# finalmouse.net
KiCad netlist of a schematic drawn in EAGLE
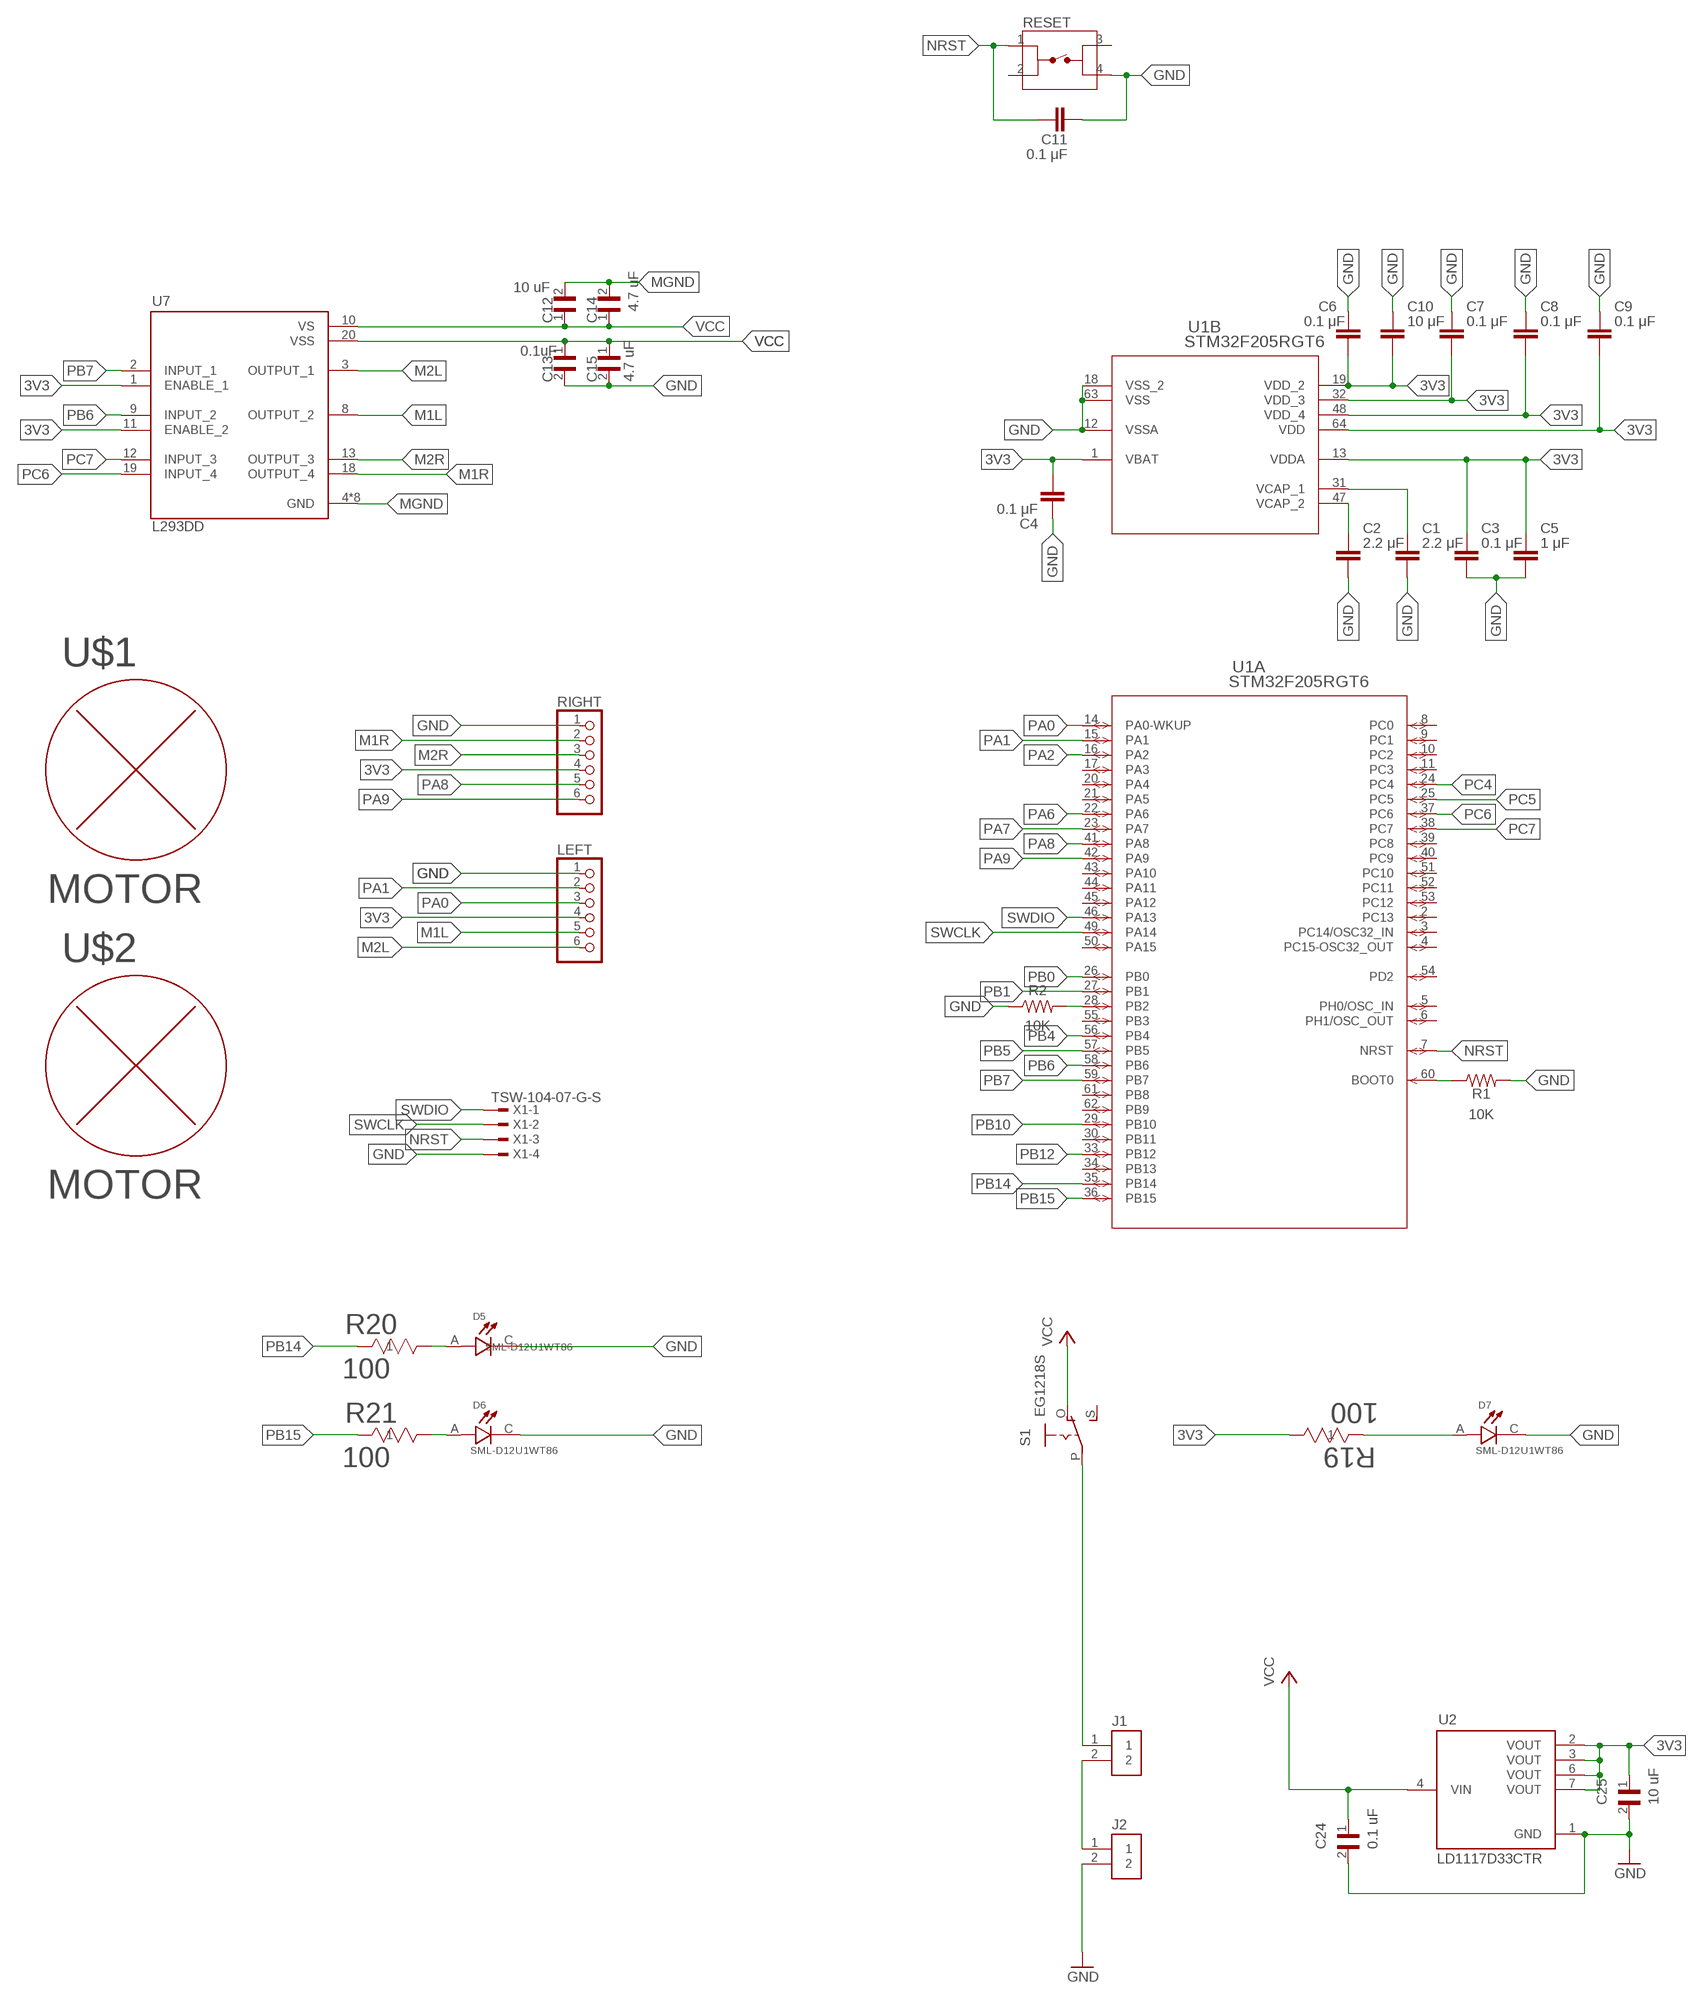
[diagram p0: schematic, sheet 1, part 1 of 2]
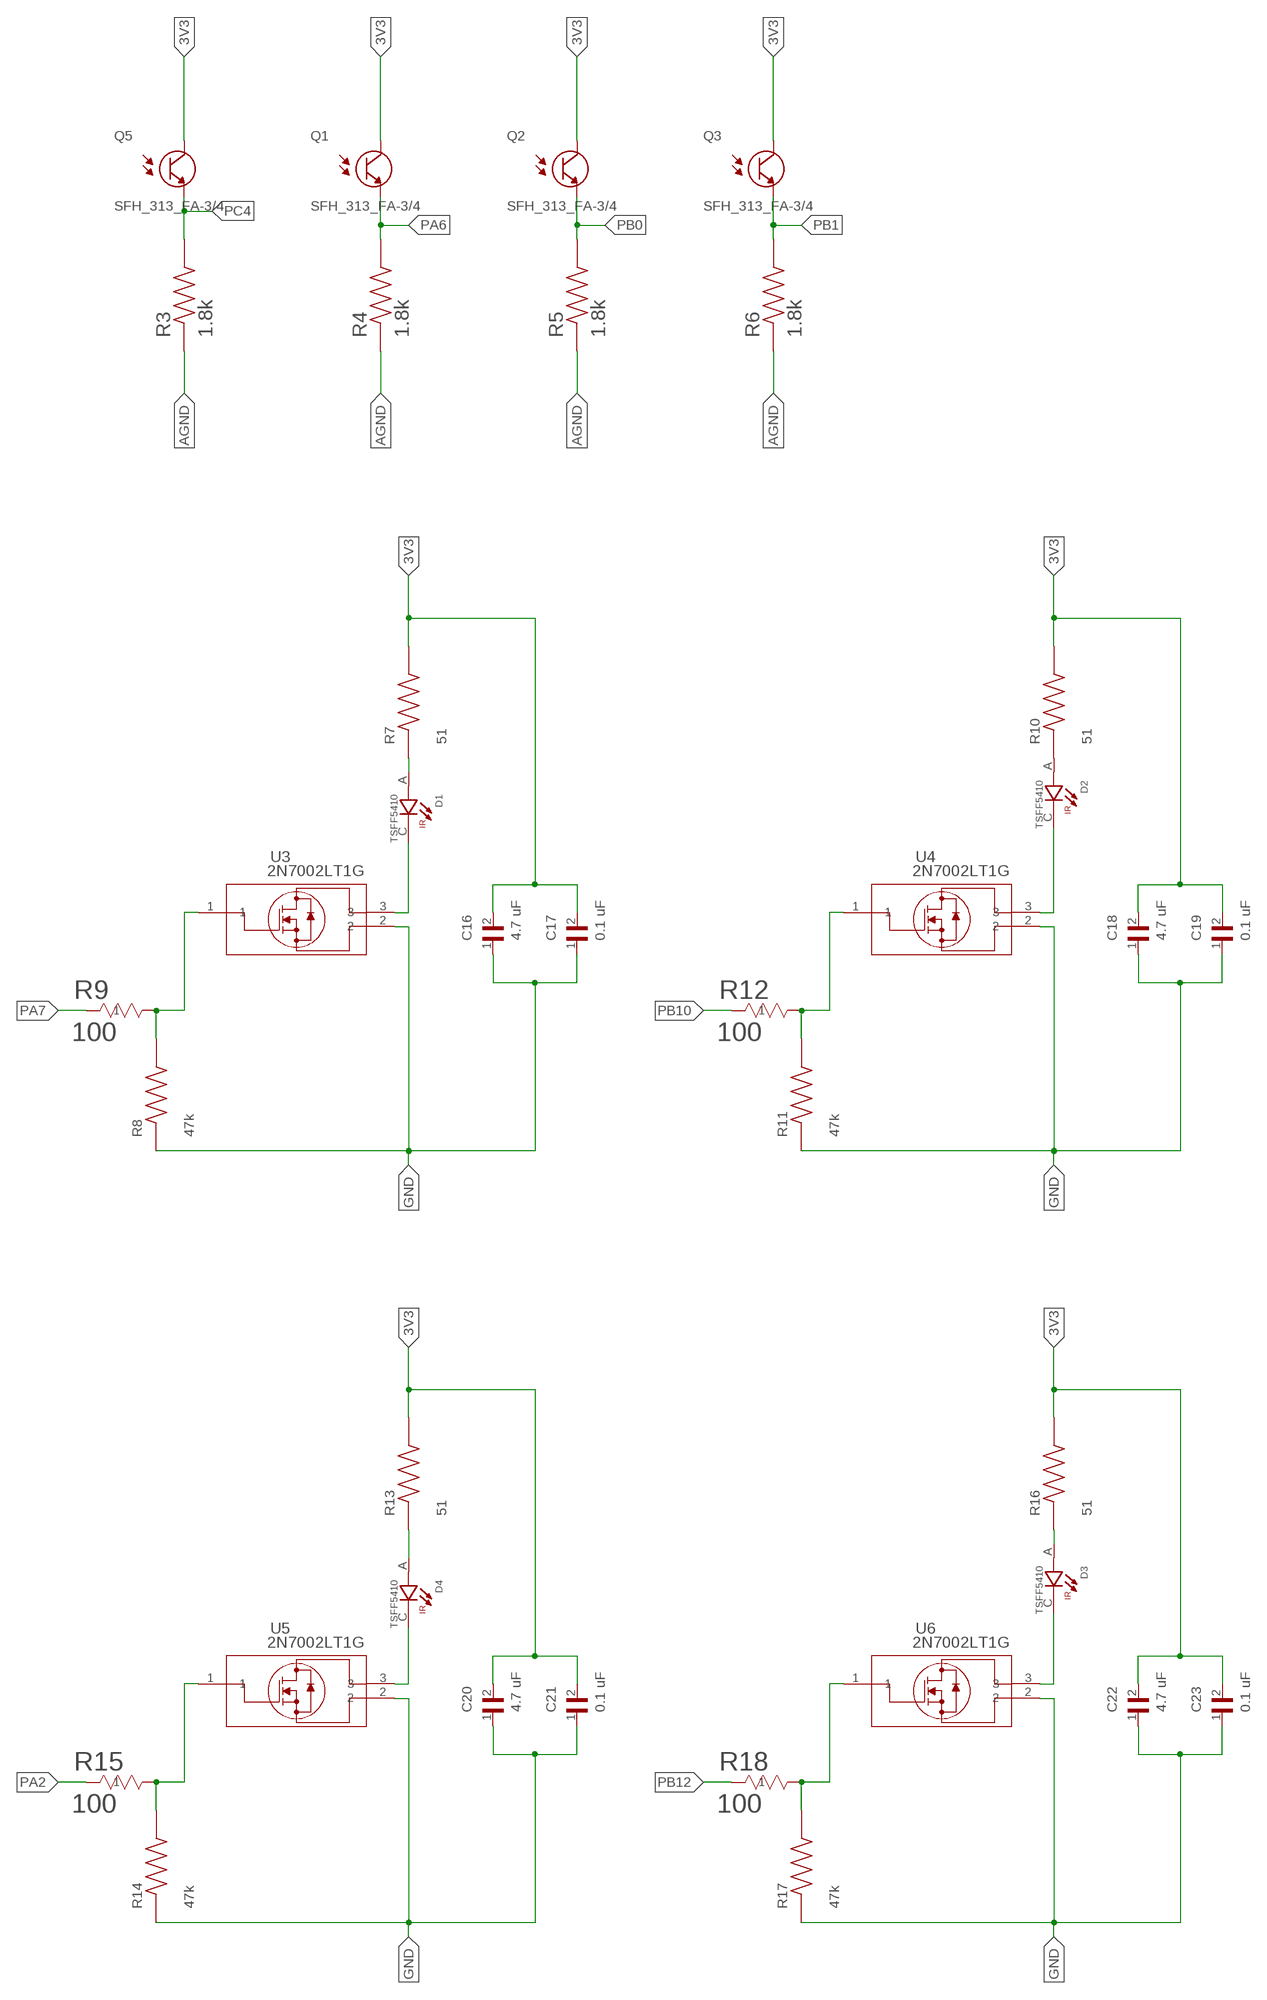
[diagram p1: schematic, sheet 1, part 2 of 2]

(export (version "E")
  (design (tool "Eeschema 10.0.6"))
  (components
    (comp (ref "C1")
      (value "2.2 μF")
      (footprint "eagle-import:CAPC1608X85")
      (libsource (lib "eagle-import") (part "CCHIP-0603(1608-METRIC)_"))
    )
    (comp (ref "C2")
      (value "2.2 μF")
      (footprint "eagle-import:CAPC1608X85")
      (libsource (lib "eagle-import") (part "CCHIP-0603(1608-METRIC)_"))
    )
    (comp (ref "C3")
      (value "0.1 μF")
      (footprint "eagle-import:CAPC1608X85")
      (libsource (lib "eagle-import") (part "CCHIP-0603(1608-METRIC)_"))
    )
    (comp (ref "C4")
      (value "0.1 μF")
      (footprint "eagle-import:CAPC1608X85")
      (libsource (lib "eagle-import") (part "CCHIP-0603(1608-METRIC)_"))
    )
    (comp (ref "C5")
      (value "1 μF")
      (footprint "eagle-import:CAPC1608X85")
      (libsource (lib "eagle-import") (part "CCHIP-0603(1608-METRIC)_"))
    )
    (comp (ref "C6")
      (value "0.1 μF")
      (footprint "eagle-import:CAPC1608X85")
      (libsource (lib "eagle-import") (part "CCHIP-0603(1608-METRIC)_"))
    )
    (comp (ref "C7")
      (value "0.1 μF")
      (footprint "eagle-import:CAPC1608X85")
      (libsource (lib "eagle-import") (part "Capacitor2_CCHIP-0603(1608-METRIC)_"))
    )
    (comp (ref "C8")
      (value "0.1 μF")
      (footprint "eagle-import:CAPC1608X85")
      (libsource (lib "eagle-import") (part "Capacitor2_CCHIP-0603(1608-METRIC)_"))
    )
    (comp (ref "C9")
      (value "0.1 μF")
      (footprint "eagle-import:CAPC1608X85")
      (libsource (lib "eagle-import") (part "Capacitor2_CCHIP-0603(1608-METRIC)_"))
    )
    (comp (ref "C10")
      (value "10 μF")
      (footprint "eagle-import:CAPC1608X85")
      (libsource (lib "eagle-import") (part "Capacitor2_CCHIP-0603(1608-METRIC)_"))
    )
    (comp (ref "C11")
      (value "0.1 μF")
      (footprint "eagle-import:CAPC1608X85")
      (libsource (lib "eagle-import") (part "Capacitor2_CCHIP-0603(1608-METRIC)_"))
    )
    (comp (ref "C12")
      (value "10 uF")
      (footprint "eagle-import:CAPC2012X135N")
      (fields
        (field (name "DIGI-KEY_PART_NUMBER") "1276-6456-2-ND")
        (field (name "MF") "Samsung Electro-Mechanics")
        (field (name "MP") "CL21A106KPFNNNG")
      )
      (libsource (lib "eagle-import") (part "CL21A106KPFNNNG"))
    )
    (comp (ref "C13")
      (value "0.1uF")
      (footprint "eagle-import:CAPC2012X94N")
      (fields
        (field (name "DIGI-KEY_PART_NUMBER") "478-5311-1-ND")
        (field (name "MF") "AVX")
        (field (name "MP") "08055C104K4T2A")
      )
      (libsource (lib "eagle-import") (part "08055C104K4T2A"))
    )
    (comp (ref "C14")
      (value "4.7 uF")
      (footprint "eagle-import:CAPC2012X145N")
      (fields
        (field (name "DIGI-KEY_PART_NUMBER") "445-11450-1-ND")
        (field (name "MF") "TDK")
        (field (name "MP") "C2012JB1C475K125AC")
      )
      (libsource (lib "eagle-import") (part "C2012JB1C475K125AC"))
    )
    (comp (ref "C15")
      (value "4.7 uF")
      (footprint "eagle-import:CAPC2012X145N")
      (fields
        (field (name "DIGI-KEY_PART_NUMBER") "445-11450-1-ND")
        (field (name "MF") "TDK")
        (field (name "MP") "C2012JB1C475K125AC")
      )
      (libsource (lib "eagle-import") (part "C2012JB1C475K125AC"))
    )
    (comp (ref "C16")
      (value "4.7 uF")
      (footprint "eagle-import:CAPC2012X145N")
      (fields
        (field (name "DIGI-KEY_PART_NUMBER") "445-11450-1-ND")
        (field (name "MF") "TDK")
        (field (name "MP") "C2012JB1C475K125AC")
      )
      (libsource (lib "eagle-import") (part "C2012JB1C475K125AC"))
    )
    (comp (ref "C17")
      (value "0.1 uF")
      (footprint "eagle-import:CAPC2012X94N")
      (fields
        (field (name "DIGI-KEY_PART_NUMBER") "478-5311-1-ND")
        (field (name "MF") "AVX")
        (field (name "MP") "08055C104K4T2A")
      )
      (libsource (lib "eagle-import") (part "08055C104K4T2A"))
    )
    (comp (ref "C18")
      (value "4.7 uF")
      (footprint "eagle-import:CAPC2012X145N")
      (fields
        (field (name "DIGI-KEY_PART_NUMBER") "445-11450-1-ND")
        (field (name "MF") "TDK")
        (field (name "MP") "C2012JB1C475K125AC")
      )
      (libsource (lib "eagle-import") (part "C2012JB1C475K125AC"))
    )
    (comp (ref "C19")
      (value "0.1 uF")
      (footprint "eagle-import:CAPC2012X94N")
      (fields
        (field (name "DIGI-KEY_PART_NUMBER") "478-5311-1-ND")
        (field (name "MF") "AVX")
        (field (name "MP") "08055C104K4T2A")
      )
      (libsource (lib "eagle-import") (part "08055C104K4T2A"))
    )
    (comp (ref "C20")
      (value "4.7 uF")
      (footprint "eagle-import:CAPC2012X145N")
      (fields
        (field (name "DIGI-KEY_PART_NUMBER") "445-11450-1-ND")
        (field (name "MF") "TDK")
        (field (name "MP") "C2012JB1C475K125AC")
      )
      (libsource (lib "eagle-import") (part "C2012JB1C475K125AC"))
    )
    (comp (ref "C21")
      (value "0.1 uF")
      (footprint "eagle-import:CAPC2012X94N")
      (fields
        (field (name "DIGI-KEY_PART_NUMBER") "478-5311-1-ND")
        (field (name "MF") "AVX")
        (field (name "MP") "08055C104K4T2A")
      )
      (libsource (lib "eagle-import") (part "08055C104K4T2A"))
    )
    (comp (ref "C22")
      (value "4.7 uF")
      (footprint "eagle-import:CAPC2012X145N")
      (fields
        (field (name "DIGI-KEY_PART_NUMBER") "445-11450-1-ND")
        (field (name "MF") "TDK")
        (field (name "MP") "C2012JB1C475K125AC")
      )
      (libsource (lib "eagle-import") (part "C2012JB1C475K125AC"))
    )
    (comp (ref "C23")
      (value "0.1 uF")
      (footprint "eagle-import:CAPC2012X94N")
      (fields
        (field (name "DIGI-KEY_PART_NUMBER") "478-5311-1-ND")
        (field (name "MF") "AVX")
        (field (name "MP") "08055C104K4T2A")
      )
      (libsource (lib "eagle-import") (part "08055C104K4T2A"))
    )
    (comp (ref "C24")
      (value "0.1 uF")
      (footprint "eagle-import:CAPC2012X135N")
      (fields
        (field (name "DIGI-KEY_PART_NUMBER") "1276-6456-2-ND")
        (field (name "MF") "Samsung Electro-Mechanics")
        (field (name "MP") "CL21A106KPFNNNG")
      )
      (libsource (lib "eagle-import") (part "CL21A106KPFNNNG"))
    )
    (comp (ref "C25")
      (value "10 uF")
      (footprint "eagle-import:CAPC2012X135N")
      (fields
        (field (name "DIGI-KEY_PART_NUMBER") "1276-2909-2-ND")
        (field (name "MF") "Samsung Electro-Mechanics")
        (field (name "MP") "CL21A226MOQNNNE")
      )
      (libsource (lib "eagle-import") (part "CL21A226MOQNNNE"))
    )
    (comp (ref "D1")
      (value "TSFF5410")
      (footprint "eagle-import:LEDRD254W55D595H1160")
      (fields (field (name "DIGI-KEY_PART_NUMBER") "751-1208-ND") (field (name "MF") "Vishay"))
      (libsource (lib "eagle-import") (part "TSFF5410"))
    )
    (comp (ref "D2")
      (value "TSFF5410")
      (footprint "eagle-import:LEDRD254W55D595H1160")
      (fields (field (name "DIGI-KEY_PART_NUMBER") "751-1208-ND") (field (name "MF") "Vishay"))
      (libsource (lib "eagle-import") (part "TSFF5410"))
    )
    (comp (ref "D3")
      (value "TSFF5410")
      (footprint "eagle-import:LEDRD254W55D595H1160")
      (fields (field (name "DIGI-KEY_PART_NUMBER") "751-1208-ND") (field (name "MF") "Vishay"))
      (libsource (lib "eagle-import") (part "TSFF5410"))
    )
    (comp (ref "D4")
      (value "TSFF5410")
      (footprint "eagle-import:LEDRD254W55D595H1160")
      (fields (field (name "DIGI-KEY_PART_NUMBER") "751-1208-ND") (field (name "MF") "Vishay"))
      (libsource (lib "eagle-import") (part "TSFF5410"))
    )
    (comp (ref "D5")
      (value "SML-D12U1WT86")
      (footprint "eagle-import:LED_SML-D12Y1WT86")
      (fields (field (name "DIGI-KEY_PART_NUMBER") "SML-D12U1WT86CT-ND") (field (name "MF") "Rohm"))
      (libsource (lib "eagle-import") (part "SML-D12U1WT86"))
    )
    (comp (ref "D6")
      (value "SML-D12U1WT86")
      (footprint "eagle-import:LED_SML-D12Y1WT86")
      (fields (field (name "DIGI-KEY_PART_NUMBER") "SML-D12U1WT86CT-ND") (field (name "MF") "Rohm"))
      (libsource (lib "eagle-import") (part "SML-D12U1WT86"))
    )
    (comp (ref "D7")
      (value "SML-D12U1WT86")
      (footprint "eagle-import:LED_SML-D12Y1WT86")
      (fields (field (name "DIGI-KEY_PART_NUMBER") "SML-D12U1WT86CT-ND") (field (name "MF") "Rohm"))
      (libsource (lib "eagle-import") (part "SML-D12U1WT86"))
    )
    (comp (ref "J1")
      (value "B2B-PH-K-S(LF)(SN)")
      (footprint "eagle-import:JST_B2B-PH-K-S(LF)(SN)")
      (fields (field (name "DIGI-KEY_PART_NUMBER") "455-1704-ND") (field (name "MF") "JST Sales"))
      (libsource (lib "eagle-import") (part "B2B-PH-K-S(LF)(SN)"))
    )
    (comp (ref "J2")
      (value "B2B-PH-K-S(LF)(SN)")
      (footprint "eagle-import:JST_B2B-PH-K-S(LF)(SN)")
      (fields (field (name "DIGI-KEY_PART_NUMBER") "455-1704-ND") (field (name "MF") "JST Sales"))
      (libsource (lib "eagle-import") (part "B2B-PH-K-S(LF)(SN)"))
    )
    (comp (ref "LEFT")
      (value "PINHD-1X6")
      (footprint "eagle-import:1X06")
      (libsource (lib "eagle-import") (part "PINHD-1X6"))
    )
    (comp (ref "Q1")
      (value "SFH_313_FA-3/4")
      (footprint "eagle-import:XDCR_SFH_313_FA-3_4")
      (fields (field (name "MF") "OSRAM Opto") (field (name "MP") "SFH 313 FA-3/4"))
      (libsource (lib "eagle-import") (part "SFH_313_FA-3/4"))
    )
    (comp (ref "Q2")
      (value "SFH_313_FA-3/4")
      (footprint "eagle-import:XDCR_SFH_313_FA-3_4")
      (fields (field (name "MF") "OSRAM Opto") (field (name "MP") "SFH 313 FA-3/4"))
      (libsource (lib "eagle-import") (part "SFH_313_FA-3/4"))
    )
    (comp (ref "Q3")
      (value "SFH_313_FA-3/4")
      (footprint "eagle-import:XDCR_SFH_313_FA-3_4")
      (fields (field (name "MF") "OSRAM Opto") (field (name "MP") "SFH 313 FA-3/4"))
      (libsource (lib "eagle-import") (part "SFH_313_FA-3/4"))
    )
    (comp (ref "Q5")
      (value "SFH_313_FA-3/4")
      (footprint "eagle-import:XDCR_SFH_313_FA-3_4")
      (fields (field (name "MF") "OSRAM Opto") (field (name "MP") "SFH 313 FA-3/4"))
      (libsource (lib "eagle-import") (part "SFH_313_FA-3/4"))
    )
    (comp (ref "R1")
      (value "10K")
      (footprint "eagle-import:RESC1608X60")
      (libsource (lib "eagle-import") (part "R-USCHIP-0603(1608-METRIC)_"))
    )
    (comp (ref "R2")
      (value "10K")
      (footprint "eagle-import:RESC1608X60")
      (libsource (lib "eagle-import") (part "R-USCHIP-0603(1608-METRIC)_"))
    )
    (comp (ref "R3")
      (value "1.8k")
      (footprint "eagle-import:RESC2012X65N")
      (fields
        (field (name "DIGI-KEY_PART_NUMBER") "RHM1.8KKCT-ND")
        (field (name "MF") "Rohm")
        (field (name "MP") "ESR10EZPJ182")
      )
      (libsource (lib "eagle-import") (part "ESR10EZPJ182"))
    )
    (comp (ref "R4")
      (value "1.8k")
      (footprint "eagle-import:RESC2012X65N")
      (fields
        (field (name "DIGI-KEY_PART_NUMBER") "RHM1.8KKCT-ND")
        (field (name "MF") "Rohm")
        (field (name "MP") "ESR10EZPJ182")
      )
      (libsource (lib "eagle-import") (part "ESR10EZPJ182"))
    )
    (comp (ref "R5")
      (value "1.8k")
      (footprint "eagle-import:RESC2012X65N")
      (fields
        (field (name "DIGI-KEY_PART_NUMBER") "RHM1.8KKCT-ND")
        (field (name "MF") "Rohm")
        (field (name "MP") "ESR10EZPJ182")
      )
      (libsource (lib "eagle-import") (part "ESR10EZPJ182"))
    )
    (comp (ref "R6")
      (value "1.8k")
      (footprint "eagle-import:RESC2012X65N")
      (fields
        (field (name "DIGI-KEY_PART_NUMBER") "RHM1.8KKCT-ND")
        (field (name "MF") "Rohm")
        (field (name "MP") "ESR10EZPJ182")
      )
      (libsource (lib "eagle-import") (part "ESR10EZPJ182"))
    )
    (comp (ref "R7")
      (value "51")
      (footprint "eagle-import:RES_ERJP06J510V")
      (fields
        (field (name "DIGI-KEY_PART_NUMBER") "P51ADCT-ND")
        (field (name "MF") "Panasonic")
        (field (name "MP") "ERJP06J510V")
      )
      (libsource (lib "eagle-import") (part "ERJP06J510V"))
    )
    (comp (ref "R8")
      (value "47k")
      (footprint "eagle-import:RES_ERA6ARB473V")
      (fields
        (field (name "DIGI-KEY_PART_NUMBER") "P47KBRCT-ND")
        (field (name "MF") "Panasonic")
        (field (name "MP") "ERA6ARB473V")
      )
      (libsource (lib "eagle-import") (part "ERA6ARB473V"))
    )
    (comp (ref "R9")
      (value "100")
      (footprint "eagle-import:RES_RK73G2A_KOA")
      (fields
        (field (name "MANUFACTURER_PART_NUMBER") "RK73G2ATTD1000D")
        (field (name "COPYRIGHT") "Copyright (C) 2022 Ultra Librarian. All rights reserved.")
      )
      (libsource (lib "eagle-import") (part "RK73G2ATTD1000D"))
    )
    (comp (ref "R10")
      (value "51")
      (footprint "eagle-import:RES_ERJP06J510V")
      (fields
        (field (name "DIGI-KEY_PART_NUMBER") "P51ADCT-ND")
        (field (name "MF") "Panasonic")
        (field (name "MP") "ERJP06J510V")
      )
      (libsource (lib "eagle-import") (part "ERJP06J510V"))
    )
    (comp (ref "R11")
      (value "47k")
      (footprint "eagle-import:RES_ERA6ARB473V")
      (fields
        (field (name "DIGI-KEY_PART_NUMBER") "P47KBRCT-ND")
        (field (name "MF") "Panasonic")
        (field (name "MP") "ERA6ARB473V")
      )
      (libsource (lib "eagle-import") (part "ERA6ARB473V"))
    )
    (comp (ref "R12")
      (value "100")
      (footprint "eagle-import:RES_RK73G2A_KOA")
      (fields
        (field (name "MANUFACTURER_PART_NUMBER") "RK73G2ATTD1000D")
        (field (name "COPYRIGHT") "Copyright (C) 2022 Ultra Librarian. All rights reserved.")
      )
      (libsource (lib "eagle-import") (part "RK73G2ATTD1000D"))
    )
    (comp (ref "R13")
      (value "51")
      (footprint "eagle-import:RES_ERJP06J510V")
      (fields
        (field (name "DIGI-KEY_PART_NUMBER") "P51ADCT-ND")
        (field (name "MF") "Panasonic")
        (field (name "MP") "ERJP06J510V")
      )
      (libsource (lib "eagle-import") (part "ERJP06J510V"))
    )
    (comp (ref "R14")
      (value "47k")
      (footprint "eagle-import:RES_ERA6ARB473V")
      (fields
        (field (name "DIGI-KEY_PART_NUMBER") "P47KBRCT-ND")
        (field (name "MF") "Panasonic")
        (field (name "MP") "ERA6ARB473V")
      )
      (libsource (lib "eagle-import") (part "ERA6ARB473V"))
    )
    (comp (ref "R15")
      (value "100")
      (footprint "eagle-import:RES_RK73G2A_KOA")
      (fields
        (field (name "MANUFACTURER_PART_NUMBER") "RK73G2ATTD1000D")
        (field (name "COPYRIGHT") "Copyright (C) 2022 Ultra Librarian. All rights reserved.")
      )
      (libsource (lib "eagle-import") (part "RK73G2ATTD1000D"))
    )
    (comp (ref "R16")
      (value "51")
      (footprint "eagle-import:RES_ERJP06J510V")
      (fields
        (field (name "DIGI-KEY_PART_NUMBER") "P51ADCT-ND")
        (field (name "MF") "Panasonic")
        (field (name "MP") "ERJP06J510V")
      )
      (libsource (lib "eagle-import") (part "ERJP06J510V"))
    )
    (comp (ref "R17")
      (value "47k")
      (footprint "eagle-import:RES_ERA6ARB473V")
      (fields
        (field (name "DIGI-KEY_PART_NUMBER") "P47KBRCT-ND")
        (field (name "MF") "Panasonic")
        (field (name "MP") "ERA6ARB473V")
      )
      (libsource (lib "eagle-import") (part "ERA6ARB473V"))
    )
    (comp (ref "R18")
      (value "100")
      (footprint "eagle-import:RES_RK73G2A_KOA")
      (fields
        (field (name "MANUFACTURER_PART_NUMBER") "RK73G2ATTD1000D")
        (field (name "COPYRIGHT") "Copyright (C) 2022 Ultra Librarian. All rights reserved.")
      )
      (libsource (lib "eagle-import") (part "RK73G2ATTD1000D"))
    )
    (comp (ref "R19")
      (value "100")
      (footprint "eagle-import:RES_RK73G2A_KOA")
      (fields
        (field (name "MANUFACTURER_PART_NUMBER") "RK73G2ATTD1000D")
        (field (name "COPYRIGHT") "Copyright (C) 2022 Ultra Librarian. All rights reserved.")
      )
      (libsource (lib "eagle-import") (part "RK73G2ATTD1000D"))
    )
    (comp (ref "R20")
      (value "100")
      (footprint "eagle-import:RES_RK73G2A_KOA")
      (fields
        (field (name "MANUFACTURER_PART_NUMBER") "RK73G2ATTD1000D")
        (field (name "COPYRIGHT") "Copyright (C) 2022 Ultra Librarian. All rights reserved.")
      )
      (libsource (lib "eagle-import") (part "RK73G2ATTD1000D"))
    )
    (comp (ref "R21")
      (value "100")
      (footprint "eagle-import:RES_RK73G2A_KOA")
      (fields
        (field (name "MANUFACTURER_PART_NUMBER") "RK73G2ATTD1000D")
        (field (name "COPYRIGHT") "Copyright (C) 2022 Ultra Librarian. All rights reserved.")
      )
      (libsource (lib "eagle-import") (part "RK73G2ATTD1000D"))
    )
    (comp (ref "RESET")
      (value "FSM4JSMA")
      (footprint "eagle-import:TE_FSM4JSMA")
      (fields
        (field (name "COMMENT") "4-1437565-1")
        (field (name "DIGI-KEY_PART_NUMBER") "450-1759-2-ND")
        (field (name "MF") "TE Connectivity")
      )
      (libsource (lib "eagle-import") (part "FSM4JSMA"))
    )
    (comp (ref "RIGHT")
      (value "PINHD-1X6")
      (footprint "eagle-import:1X06")
      (libsource (lib "eagle-import") (part "PINHD-1X6"))
    )
    (comp (ref "S1")
      (value "EG1218S")
      (footprint "eagle-import:EG1218")
      (fields
        (field (name "DIGI-KEY_PART_NUMBER") "EG1218A-ND")
        (field (name "MF") "E-Switch")
        (field (name "MP") "EG1218")
      )
      (libsource (lib "eagle-import") (part "EG1218S"))
    )
    (comp (ref "U$1")
      (value "MOTOR")
      (footprint "eagle-import:MOTOR")
      (libsource (lib "eagle-import") (part "MOTOR"))
    )
    (comp (ref "U$2")
      (value "MOTOR")
      (footprint "eagle-import:MOTOR")
      (libsource (lib "eagle-import") (part "MOTOR"))
    )
    (comp (ref "U1")
      (value "STM32F205RGT6")
      (footprint "eagle-import:LQFP64-10X10MM")
      (fields (field (name "COPYRIGHT") "Copyright (C) 2021 Ultra Librarian. All rights reserved."))
      (libsource (lib "eagle-import") (part "STM32F205RGT6"))
    )
    (comp (ref "U2")
      (value "LD1117D33CTR")
      (footprint "eagle-import:SOIC127P600X175-8N")
      (fields (field (name "DIGI-KEY_PART_NUMBER") "497-1230-1-ND") (field (name "MF") "STMicroelectronics"))
      (libsource (lib "eagle-import") (part "LD1117D33CTR"))
    )
    (comp (ref "U3")
      (value "2N7002LT1G")
      (footprint "eagle-import:SOT-23_3L_ONS")
      (fields (field (name "COPYRIGHT") "Copyright (C) 2022 Ultra Librarian. All rights reserved."))
      (libsource (lib "eagle-import") (part "2N7002LT1G"))
    )
    (comp (ref "U4")
      (value "2N7002LT1G")
      (footprint "eagle-import:SOT-23_3L_ONS")
      (fields (field (name "COPYRIGHT") "Copyright (C) 2022 Ultra Librarian. All rights reserved."))
      (libsource (lib "eagle-import") (part "2N7002LT1G"))
    )
    (comp (ref "U5")
      (value "2N7002LT1G")
      (footprint "eagle-import:SOT-23_3L_ONS")
      (fields (field (name "COPYRIGHT") "Copyright (C) 2022 Ultra Librarian. All rights reserved."))
      (libsource (lib "eagle-import") (part "2N7002LT1G"))
    )
    (comp (ref "U6")
      (value "2N7002LT1G")
      (footprint "eagle-import:SOT-23_3L_ONS")
      (fields (field (name "COPYRIGHT") "Copyright (C) 2022 Ultra Librarian. All rights reserved."))
      (libsource (lib "eagle-import") (part "2N7002LT1G"))
    )
    (comp (ref "U7")
      (value "L293DD")
      (footprint "eagle-import:SOIC127P1032X265-20N")
      (fields (field (name "DIGI-KEY_PART_NUMBER") "497-2937-2-ND") (field (name "MF") "STMicroelectronics"))
      (libsource (lib "eagle-import") (part "L293DD"))
    )
    (comp (ref "X1")
      (value "TSW-104-07-G-S")
      (footprint "eagle-import:TSW-104-XX-G-S")
      (fields (field (name "MF") "Samtec Inc."))
      (libsource (lib "eagle-import") (part "TSW-104--G-S07"))
    )
  )
  (nets
    (net (code "1") (name "3V3") (class "Default")
      (node (ref "C10") (pin "2") (pinfunction "2_2") (pintype "passive"))
      (node (ref "C16") (pin "2") (pinfunction "2_2") (pintype "passive"))
      (node (ref "C17") (pin "2") (pinfunction "2_2") (pintype "passive"))
      (node (ref "C18") (pin "2") (pinfunction "2_2") (pintype "passive"))
      (node (ref "C19") (pin "2") (pinfunction "2_2") (pintype "passive"))
      (node (ref "C20") (pin "2") (pinfunction "2_2") (pintype "passive"))
      (node (ref "C21") (pin "2") (pinfunction "2_2") (pintype "passive"))
      (node (ref "C22") (pin "2") (pinfunction "2_2") (pintype "passive"))
      (node (ref "C23") (pin "2") (pinfunction "2_2") (pintype "passive"))
      (node (ref "C25") (pin "1") (pinfunction "1_1") (pintype "passive"))
      (node (ref "C3") (pin "1") (pinfunction "1_1") (pintype "passive"))
      (node (ref "C4") (pin "2") (pinfunction "2_2") (pintype "passive"))
      (node (ref "C5") (pin "1") (pinfunction "1_1") (pintype "passive"))
      (node (ref "C6") (pin "2") (pinfunction "2_2") (pintype "passive"))
      (node (ref "C7") (pin "2") (pinfunction "2_2") (pintype "passive"))
      (node (ref "C8") (pin "2") (pinfunction "2_2") (pintype "passive"))
      (node (ref "C9") (pin "2") (pinfunction "2_2") (pintype "passive"))
      (node (ref "LEFT") (pin "4") (pinfunction "4_4") (pintype "passive"))
      (node (ref "Q1") (pin "2") (pinfunction "C_2") (pintype "passive"))
      (node (ref "Q2") (pin "2") (pinfunction "C_2") (pintype "passive"))
      (node (ref "Q3") (pin "2") (pinfunction "C_2") (pintype "passive"))
      (node (ref "Q5") (pin "2") (pinfunction "C_2") (pintype "passive"))
      (node (ref "R10") (pin "2") (pinfunction "2_2") (pintype "passive"))
      (node (ref "R13") (pin "2") (pinfunction "2_2") (pintype "passive"))
      (node (ref "R16") (pin "2") (pinfunction "2_2") (pintype "passive"))
      (node (ref "R19") (pin "2") (pinfunction "2_2") (pintype "passive"))
      (node (ref "R7") (pin "2") (pinfunction "2_2") (pintype "passive"))
      (node (ref "RIGHT") (pin "4") (pinfunction "4_4") (pintype "passive"))
      (node (ref "U1") (pin "1") (pinfunction "VBAT_1") (pintype "power_in"))
      (node (ref "U1") (pin "13") (pinfunction "VDDA_13") (pintype "power_in"))
      (node (ref "U1") (pin "19") (pinfunction "VDD_2_19") (pintype "power_in"))
      (node (ref "U1") (pin "32") (pinfunction "VDD_3_32") (pintype "power_in"))
      (node (ref "U1") (pin "48") (pinfunction "VDD_4_48") (pintype "power_in"))
      (node (ref "U1") (pin "64") (pinfunction "VDD_64") (pintype "power_in"))
      (node (ref "U2") (pin "2") (pinfunction "VOUT_2") (pintype "output"))
      (node (ref "U2") (pin "3") (pinfunction "VOUT_3") (pintype "output"))
      (node (ref "U2") (pin "6") (pinfunction "VOUT_6") (pintype "output"))
      (node (ref "U2") (pin "7") (pinfunction "VOUT_7") (pintype "output"))
      (node (ref "U7") (pin "1") (pinfunction "ENABLE_1_1") (pintype "input"))
      (node (ref "U7") (pin "11") (pinfunction "ENABLE_2_11") (pintype "input"))
    )
    (net (code "2") (name "AGND") (class "Default")
      (node (ref "R3") (pin "1") (pinfunction "1_1") (pintype "passive"))
      (node (ref "R4") (pin "1") (pinfunction "1_1") (pintype "passive"))
      (node (ref "R5") (pin "1") (pinfunction "1_1") (pintype "passive"))
      (node (ref "R6") (pin "1") (pinfunction "1_1") (pintype "passive"))
    )
    (net (code "3") (name "GND") (class "Default")
      (node (ref "C1") (pin "2") (pinfunction "2_2") (pintype "passive"))
      (node (ref "C10") (pin "1") (pinfunction "1_1") (pintype "passive"))
      (node (ref "C11") (pin "2") (pinfunction "2_2") (pintype "passive"))
      (node (ref "C13") (pin "2") (pinfunction "2_2") (pintype "passive"))
      (node (ref "C15") (pin "2") (pinfunction "2_2") (pintype "passive"))
      (node (ref "C16") (pin "1") (pinfunction "1_1") (pintype "passive"))
      (node (ref "C17") (pin "1") (pinfunction "1_1") (pintype "passive"))
      (node (ref "C18") (pin "1") (pinfunction "1_1") (pintype "passive"))
      (node (ref "C19") (pin "1") (pinfunction "1_1") (pintype "passive"))
      (node (ref "C2") (pin "2") (pinfunction "2_2") (pintype "passive"))
      (node (ref "C20") (pin "1") (pinfunction "1_1") (pintype "passive"))
      (node (ref "C21") (pin "1") (pinfunction "1_1") (pintype "passive"))
      (node (ref "C22") (pin "1") (pinfunction "1_1") (pintype "passive"))
      (node (ref "C23") (pin "1") (pinfunction "1_1") (pintype "passive"))
      (node (ref "C24") (pin "2") (pinfunction "2_2") (pintype "passive"))
      (node (ref "C25") (pin "2") (pinfunction "2_2") (pintype "passive"))
      (node (ref "C3") (pin "2") (pinfunction "2_2") (pintype "passive"))
      (node (ref "C4") (pin "1") (pinfunction "1_1") (pintype "passive"))
      (node (ref "C5") (pin "2") (pinfunction "2_2") (pintype "passive"))
      (node (ref "C6") (pin "1") (pinfunction "1_1") (pintype "passive"))
      (node (ref "C7") (pin "1") (pinfunction "1_1") (pintype "passive"))
      (node (ref "C8") (pin "1") (pinfunction "1_1") (pintype "passive"))
      (node (ref "C9") (pin "1") (pinfunction "1_1") (pintype "passive"))
      (node (ref "D5") (pin "C") (pinfunction "C_C") (pintype "passive"))
      (node (ref "D6") (pin "C") (pinfunction "C_C") (pintype "passive"))
      (node (ref "D7") (pin "C") (pinfunction "C_C") (pintype "passive"))
      (node (ref "J2") (pin "2") (pinfunction "2_2") (pintype "passive"))
      (node (ref "LEFT") (pin "1") (pinfunction "1_1") (pintype "passive"))
      (node (ref "R1") (pin "2") (pinfunction "2_2") (pintype "passive"))
      (node (ref "R11") (pin "1") (pinfunction "1_1") (pintype "passive"))
      (node (ref "R14") (pin "1") (pinfunction "1_1") (pintype "passive"))
      (node (ref "R17") (pin "1") (pinfunction "1_1") (pintype "passive"))
      (node (ref "R2") (pin "1") (pinfunction "1_1") (pintype "passive"))
      (node (ref "R8") (pin "1") (pinfunction "1_1") (pintype "passive"))
      (node (ref "RESET") (pin "4") (pinfunction "4_4") (pintype "passive"))
      (node (ref "RIGHT") (pin "1") (pinfunction "1_1") (pintype "passive"))
      (node (ref "U1") (pin "12") (pinfunction "VSSA_12") (pintype "power_in"))
      (node (ref "U1") (pin "18") (pinfunction "VSS_2_18") (pintype "power_in"))
      (node (ref "U1") (pin "63") (pinfunction "VSS_63") (pintype "power_in"))
      (node (ref "U2") (pin "1") (pinfunction "GND_1") (pintype "power_in"))
      (node (ref "U3") (pin "2") (pinfunction "2_2") (pintype "passive"))
      (node (ref "U4") (pin "2") (pinfunction "2_2") (pintype "passive"))
      (node (ref "U5") (pin "2") (pinfunction "2_2") (pintype "passive"))
      (node (ref "U6") (pin "2") (pinfunction "2_2") (pintype "passive"))
      (node (ref "X1") (pin "4") (pinfunction "1_4") (pintype "passive"))
    )
    (net (code "4") (name "M1L") (class "Default")
      (node (ref "LEFT") (pin "5") (pinfunction "5_5") (pintype "passive"))
      (node (ref "U7") (pin "8") (pinfunction "OUTPUT_2_8") (pintype "output"))
    )
    (net (code "5") (name "M1R") (class "Default")
      (node (ref "RIGHT") (pin "2") (pinfunction "2_2") (pintype "passive"))
      (node (ref "U7") (pin "18") (pinfunction "OUTPUT_4_18") (pintype "output"))
    )
    (net (code "6") (name "M2L") (class "Default")
      (node (ref "LEFT") (pin "6") (pinfunction "6_6") (pintype "passive"))
      (node (ref "U7") (pin "3") (pinfunction "OUTPUT_1_3") (pintype "output"))
    )
    (net (code "7") (name "M2R") (class "Default")
      (node (ref "RIGHT") (pin "3") (pinfunction "3_3") (pintype "passive"))
      (node (ref "U7") (pin "13") (pinfunction "OUTPUT_3_13") (pintype "output"))
    )
    (net (code "8") (name "MGND") (class "Default")
      (node (ref "C12") (pin "2") (pinfunction "2_2") (pintype "passive"))
      (node (ref "C14") (pin "2") (pinfunction "2_2") (pintype "passive"))
      (node (ref "U7") (pin "14") (pinfunction "GND_14") (pintype "power_in"))
      (node (ref "U7") (pin "15") (pinfunction "GND_15") (pintype "power_in"))
      (node (ref "U7") (pin "16") (pinfunction "GND_16") (pintype "power_in"))
      (node (ref "U7") (pin "17") (pinfunction "GND_17") (pintype "power_in"))
      (node (ref "U7") (pin "4") (pinfunction "GND_4") (pintype "power_in"))
      (node (ref "U7") (pin "5") (pinfunction "GND_5") (pintype "power_in"))
      (node (ref "U7") (pin "6") (pinfunction "GND_6") (pintype "power_in"))
      (node (ref "U7") (pin "7") (pinfunction "GND_7") (pintype "power_in"))
    )
    (net (code "9") (name "NRST") (class "Default")
      (node (ref "C11") (pin "1") (pinfunction "1_1") (pintype "passive"))
      (node (ref "RESET") (pin "1") (pinfunction "1_1") (pintype "passive"))
      (node (ref "U1") (pin "7") (pinfunction "NRST_7") (pintype "bidirectional"))
      (node (ref "X1") (pin "3") (pinfunction "1_3") (pintype "passive"))
    )
    (net (code "10") (name "Net-(D1-PadA)") (class "Default")
      (node (ref "D1") (pin "A") (pinfunction "A_A") (pintype "passive"))
      (node (ref "R7") (pin "1") (pinfunction "1_1") (pintype "passive"))
    )
    (net (code "11") (name "Net-(D1-PadC)") (class "Default")
      (node (ref "D1") (pin "C") (pinfunction "C_C") (pintype "passive"))
      (node (ref "U3") (pin "3") (pinfunction "3_3") (pintype "passive"))
    )
    (net (code "12") (name "Net-(D2-PadA)") (class "Default")
      (node (ref "D2") (pin "A") (pinfunction "A_A") (pintype "passive"))
      (node (ref "R10") (pin "1") (pinfunction "1_1") (pintype "passive"))
    )
    (net (code "13") (name "Net-(D2-PadC)") (class "Default")
      (node (ref "D2") (pin "C") (pinfunction "C_C") (pintype "passive"))
      (node (ref "U4") (pin "3") (pinfunction "3_3") (pintype "passive"))
    )
    (net (code "14") (name "Net-(D3-PadA)") (class "Default")
      (node (ref "D3") (pin "A") (pinfunction "A_A") (pintype "passive"))
      (node (ref "R16") (pin "1") (pinfunction "1_1") (pintype "passive"))
    )
    (net (code "15") (name "Net-(D3-PadC)") (class "Default")
      (node (ref "D3") (pin "C") (pinfunction "C_C") (pintype "passive"))
      (node (ref "U6") (pin "3") (pinfunction "3_3") (pintype "passive"))
    )
    (net (code "16") (name "Net-(D4-PadA)") (class "Default")
      (node (ref "D4") (pin "A") (pinfunction "A_A") (pintype "passive"))
      (node (ref "R13") (pin "1") (pinfunction "1_1") (pintype "passive"))
    )
    (net (code "17") (name "Net-(D4-PadC)") (class "Default")
      (node (ref "D4") (pin "C") (pinfunction "C_C") (pintype "passive"))
      (node (ref "U5") (pin "3") (pinfunction "3_3") (pintype "passive"))
    )
    (net (code "18") (name "Net-(D5-PadA)") (class "Default")
      (node (ref "D5") (pin "A") (pinfunction "A_A") (pintype "passive"))
      (node (ref "R20") (pin "2") (pinfunction "2_2") (pintype "passive"))
    )
    (net (code "19") (name "Net-(D6-PadA)") (class "Default")
      (node (ref "D6") (pin "A") (pinfunction "A_A") (pintype "passive"))
      (node (ref "R21") (pin "2") (pinfunction "2_2") (pintype "passive"))
    )
    (net (code "20") (name "Net-(D7-PadA)") (class "Default")
      (node (ref "D7") (pin "A") (pinfunction "A_A") (pintype "passive"))
      (node (ref "R19") (pin "1") (pinfunction "1_1") (pintype "passive"))
    )
    (net (code "21") (name "Net-(J1-Pad1)") (class "Default")
      (node (ref "J1") (pin "1") (pinfunction "1_1") (pintype "passive"))
      (node (ref "S1") (pin "P") (pinfunction "P_P") (pintype "passive"))
    )
    (net (code "22") (name "Net-(J1-Pad2)") (class "Default")
      (node (ref "J1") (pin "2") (pinfunction "2_2") (pintype "passive"))
      (node (ref "J2") (pin "1") (pinfunction "1_1") (pintype "passive"))
    )
    (net (code "23") (name "Net-(R8-Pad2)") (class "Default")
      (node (ref "R8") (pin "2") (pinfunction "2_2") (pintype "passive"))
      (node (ref "R9") (pin "2") (pinfunction "2_2") (pintype "passive"))
      (node (ref "U3") (pin "1") (pinfunction "1_1") (pintype "passive"))
    )
    (net (code "24") (name "Net-(R11-Pad2)") (class "Default")
      (node (ref "R11") (pin "2") (pinfunction "2_2") (pintype "passive"))
      (node (ref "R12") (pin "2") (pinfunction "2_2") (pintype "passive"))
      (node (ref "U4") (pin "1") (pinfunction "1_1") (pintype "passive"))
    )
    (net (code "25") (name "Net-(R14-Pad2)") (class "Default")
      (node (ref "R14") (pin "2") (pinfunction "2_2") (pintype "passive"))
      (node (ref "R15") (pin "2") (pinfunction "2_2") (pintype "passive"))
      (node (ref "U5") (pin "1") (pinfunction "1_1") (pintype "passive"))
    )
    (net (code "26") (name "Net-(R17-Pad2)") (class "Default")
      (node (ref "R17") (pin "2") (pinfunction "2_2") (pintype "passive"))
      (node (ref "R18") (pin "2") (pinfunction "2_2") (pintype "passive"))
      (node (ref "U6") (pin "1") (pinfunction "1_1") (pintype "passive"))
    )
    (net (code "27") (name "Net-(U1A-BOOT0)") (class "Default")
      (node (ref "R1") (pin "1") (pinfunction "1_1") (pintype "passive"))
      (node (ref "U1") (pin "60") (pinfunction "BOOT0_60") (pintype "input"))
    )
    (net (code "28") (name "Net-(U1A-PB2)") (class "Default")
      (node (ref "R2") (pin "2") (pinfunction "2_2") (pintype "passive"))
      (node (ref "U1") (pin "28") (pinfunction "PB2_28") (pintype "bidirectional"))
    )
    (net (code "29") (name "Net-(U1B-VCAP_1)") (class "Default")
      (node (ref "C1") (pin "1") (pinfunction "1_1") (pintype "passive"))
      (node (ref "U1") (pin "31") (pinfunction "VCAP_1_31") (pintype "power_in"))
    )
    (net (code "30") (name "Net-(U1B-VCAP_2)") (class "Default")
      (node (ref "C2") (pin "1") (pinfunction "1_1") (pintype "passive"))
      (node (ref "U1") (pin "47") (pinfunction "VCAP_2_47") (pintype "power_in"))
    )
    (net (code "31") (name "PA0") (class "Default")
      (node (ref "LEFT") (pin "3") (pinfunction "3_3") (pintype "passive"))
      (node (ref "U1") (pin "14") (pinfunction "PA0-WKUP_14") (pintype "bidirectional"))
    )
    (net (code "32") (name "PA1") (class "Default")
      (node (ref "LEFT") (pin "2") (pinfunction "2_2") (pintype "passive"))
      (node (ref "U1") (pin "15") (pinfunction "PA1_15") (pintype "bidirectional"))
    )
    (net (code "33") (name "PA2") (class "Default")
      (node (ref "R15") (pin "1") (pinfunction "1_1") (pintype "passive"))
      (node (ref "U1") (pin "16") (pinfunction "PA2_16") (pintype "bidirectional"))
    )
    (net (code "34") (name "PA6") (class "Default")
      (node (ref "Q1") (pin "1") (pinfunction "E_1") (pintype "passive"))
      (node (ref "R4") (pin "2") (pinfunction "2_2") (pintype "passive"))
      (node (ref "U1") (pin "22") (pinfunction "PA6_22") (pintype "bidirectional"))
    )
    (net (code "35") (name "PA7") (class "Default")
      (node (ref "R9") (pin "1") (pinfunction "1_1") (pintype "passive"))
      (node (ref "U1") (pin "23") (pinfunction "PA7_23") (pintype "bidirectional"))
    )
    (net (code "36") (name "PA8") (class "Default")
      (node (ref "RIGHT") (pin "5") (pinfunction "5_5") (pintype "passive"))
      (node (ref "U1") (pin "41") (pinfunction "PA8_41") (pintype "bidirectional"))
    )
    (net (code "37") (name "PA9") (class "Default")
      (node (ref "RIGHT") (pin "6") (pinfunction "6_6") (pintype "passive"))
      (node (ref "U1") (pin "42") (pinfunction "PA9_42") (pintype "bidirectional"))
    )
    (net (code "38") (name "PB0") (class "Default")
      (node (ref "Q2") (pin "1") (pinfunction "E_1") (pintype "passive"))
      (node (ref "R5") (pin "2") (pinfunction "2_2") (pintype "passive"))
      (node (ref "U1") (pin "26") (pinfunction "PB0_26") (pintype "bidirectional"))
    )
    (net (code "39") (name "PB1") (class "Default")
      (node (ref "Q3") (pin "1") (pinfunction "E_1") (pintype "passive"))
      (node (ref "R6") (pin "2") (pinfunction "2_2") (pintype "passive"))
      (node (ref "U1") (pin "27") (pinfunction "PB1_27") (pintype "bidirectional"))
    )
    (net (code "40") (name "PB4") (class "Default")
      (node (ref "U1") (pin "56") (pinfunction "PB4_56") (pintype "bidirectional"))
    )
    (net (code "41") (name "PB5") (class "Default")
      (node (ref "U1") (pin "57") (pinfunction "PB5_57") (pintype "bidirectional"))
    )
    (net (code "42") (name "PB6") (class "Default")
      (node (ref "U1") (pin "58") (pinfunction "PB6_58") (pintype "bidirectional"))
      (node (ref "U7") (pin "9") (pinfunction "INPUT_2_9") (pintype "input"))
    )
    (net (code "43") (name "PB7") (class "Default")
      (node (ref "U1") (pin "59") (pinfunction "PB7_59") (pintype "bidirectional"))
      (node (ref "U7") (pin "2") (pinfunction "INPUT_1_2") (pintype "input"))
    )
    (net (code "44") (name "PB10") (class "Default")
      (node (ref "R12") (pin "1") (pinfunction "1_1") (pintype "passive"))
      (node (ref "U1") (pin "29") (pinfunction "PB10_29") (pintype "bidirectional"))
    )
    (net (code "45") (name "PB12") (class "Default")
      (node (ref "R18") (pin "1") (pinfunction "1_1") (pintype "passive"))
      (node (ref "U1") (pin "33") (pinfunction "PB12_33") (pintype "bidirectional"))
    )
    (net (code "46") (name "PB14") (class "Default")
      (node (ref "R20") (pin "1") (pinfunction "1_1") (pintype "passive"))
      (node (ref "U1") (pin "35") (pinfunction "PB14_35") (pintype "bidirectional"))
    )
    (net (code "47") (name "PB15") (class "Default")
      (node (ref "R21") (pin "1") (pinfunction "1_1") (pintype "passive"))
      (node (ref "U1") (pin "36") (pinfunction "PB15_36") (pintype "bidirectional"))
    )
    (net (code "48") (name "PC4") (class "Default")
      (node (ref "Q5") (pin "1") (pinfunction "E_1") (pintype "passive"))
      (node (ref "R3") (pin "2") (pinfunction "2_2") (pintype "passive"))
      (node (ref "U1") (pin "24") (pinfunction "PC4_24") (pintype "bidirectional"))
    )
    (net (code "49") (name "PC5") (class "Default")
      (node (ref "U1") (pin "25") (pinfunction "PC5_25") (pintype "bidirectional"))
    )
    (net (code "50") (name "PC6") (class "Default")
      (node (ref "U1") (pin "37") (pinfunction "PC6_37") (pintype "bidirectional"))
      (node (ref "U7") (pin "19") (pinfunction "INPUT_4_19") (pintype "input"))
    )
    (net (code "51") (name "PC7") (class "Default")
      (node (ref "U1") (pin "38") (pinfunction "PC7_38") (pintype "bidirectional"))
      (node (ref "U7") (pin "12") (pinfunction "INPUT_3_12") (pintype "input"))
    )
    (net (code "52") (name "SWCLK") (class "Default")
      (node (ref "U1") (pin "49") (pinfunction "PA14_49") (pintype "bidirectional"))
      (node (ref "X1") (pin "2") (pinfunction "1_2") (pintype "passive"))
    )
    (net (code "53") (name "SWDIO") (class "Default")
      (node (ref "U1") (pin "46") (pinfunction "PA13_46") (pintype "bidirectional"))
      (node (ref "X1") (pin "1") (pinfunction "1_1") (pintype "passive"))
    )
    (net (code "54") (name "VCC") (class "Default")
      (node (ref "C12") (pin "1") (pinfunction "1_1") (pintype "passive"))
      (node (ref "C13") (pin "1") (pinfunction "1_1") (pintype "passive"))
      (node (ref "C14") (pin "1") (pinfunction "1_1") (pintype "passive"))
      (node (ref "C15") (pin "1") (pinfunction "1_1") (pintype "passive"))
      (node (ref "C24") (pin "1") (pinfunction "1_1") (pintype "passive"))
      (node (ref "S1") (pin "O") (pinfunction "O_O") (pintype "passive"))
      (node (ref "U2") (pin "4") (pinfunction "VIN_4") (pintype "input"))
      (node (ref "U7") (pin "10") (pinfunction "VS_10") (pintype "power_in"))
      (node (ref "U7") (pin "20") (pinfunction "VSS_20") (pintype "power_in"))
    )
    (net (code "55") (name "unconnected-(RESET-Pad2)") (class "Default")
      (node (ref "RESET") (pin "2") (pinfunction "2_2") (pintype "passive"))
    )
    (net (code "56") (name "unconnected-(RESET-Pad3)") (class "Default")
      (node (ref "RESET") (pin "3") (pinfunction "3_3") (pintype "passive"))
    )
    (net (code "57") (name "unconnected-(S1-PadS)") (class "Default")
      (node (ref "S1") (pin "S") (pinfunction "S_S") (pintype "passive"))
    )
    (net (code "58") (name "unconnected-(U1A-PA3-Pad17)") (class "Default")
      (node (ref "U1") (pin "17") (pinfunction "PA3_17") (pintype "bidirectional"))
    )
    (net (code "59") (name "unconnected-(U1A-PA4-Pad20)") (class "Default")
      (node (ref "U1") (pin "20") (pinfunction "PA4_20") (pintype "bidirectional"))
    )
    (net (code "60") (name "unconnected-(U1A-PA5-Pad21)") (class "Default")
      (node (ref "U1") (pin "21") (pinfunction "PA5_21") (pintype "bidirectional"))
    )
    (net (code "61") (name "unconnected-(U1A-PA10-Pad43)") (class "Default")
      (node (ref "U1") (pin "43") (pinfunction "PA10_43") (pintype "bidirectional"))
    )
    (net (code "62") (name "unconnected-(U1A-PA11-Pad44)") (class "Default")
      (node (ref "U1") (pin "44") (pinfunction "PA11_44") (pintype "bidirectional"))
    )
    (net (code "63") (name "unconnected-(U1A-PA12-Pad45)") (class "Default")
      (node (ref "U1") (pin "45") (pinfunction "PA12_45") (pintype "bidirectional"))
    )
    (net (code "64") (name "unconnected-(U1A-PA15-Pad50)") (class "Default")
      (node (ref "U1") (pin "50") (pinfunction "PA15_50") (pintype "bidirectional"))
    )
    (net (code "65") (name "unconnected-(U1A-PB3-Pad55)") (class "Default")
      (node (ref "U1") (pin "55") (pinfunction "PB3_55") (pintype "bidirectional"))
    )
    (net (code "66") (name "unconnected-(U1A-PB8-Pad61)") (class "Default")
      (node (ref "U1") (pin "61") (pinfunction "PB8_61") (pintype "bidirectional"))
    )
    (net (code "67") (name "unconnected-(U1A-PB9-Pad62)") (class "Default")
      (node (ref "U1") (pin "62") (pinfunction "PB9_62") (pintype "bidirectional"))
    )
    (net (code "68") (name "unconnected-(U1A-PB11-Pad30)") (class "Default")
      (node (ref "U1") (pin "30") (pinfunction "PB11_30") (pintype "bidirectional"))
    )
    (net (code "69") (name "unconnected-(U1A-PB13-Pad34)") (class "Default")
      (node (ref "U1") (pin "34") (pinfunction "PB13_34") (pintype "bidirectional"))
    )
    (net (code "70") (name "unconnected-(U1A-PC0-Pad8)") (class "Default")
      (node (ref "U1") (pin "8") (pinfunction "PC0_8") (pintype "bidirectional"))
    )
    (net (code "71") (name "unconnected-(U1A-PC1-Pad9)") (class "Default")
      (node (ref "U1") (pin "9") (pinfunction "PC1_9") (pintype "bidirectional"))
    )
    (net (code "72") (name "unconnected-(U1A-PC2-Pad10)") (class "Default")
      (node (ref "U1") (pin "10") (pinfunction "PC2_10") (pintype "bidirectional"))
    )
    (net (code "73") (name "unconnected-(U1A-PC3-Pad11)") (class "Default")
      (node (ref "U1") (pin "11") (pinfunction "PC3_11") (pintype "bidirectional"))
    )
    (net (code "74") (name "unconnected-(U1A-PC8-Pad39)") (class "Default")
      (node (ref "U1") (pin "39") (pinfunction "PC8_39") (pintype "bidirectional"))
    )
    (net (code "75") (name "unconnected-(U1A-PC9-Pad40)") (class "Default")
      (node (ref "U1") (pin "40") (pinfunction "PC9_40") (pintype "bidirectional"))
    )
    (net (code "76") (name "unconnected-(U1A-PC10-Pad51)") (class "Default")
      (node (ref "U1") (pin "51") (pinfunction "PC10_51") (pintype "bidirectional"))
    )
    (net (code "77") (name "unconnected-(U1A-PC11-Pad52)") (class "Default")
      (node (ref "U1") (pin "52") (pinfunction "PC11_52") (pintype "bidirectional"))
    )
    (net (code "78") (name "unconnected-(U1A-PC12-Pad53)") (class "Default")
      (node (ref "U1") (pin "53") (pinfunction "PC12_53") (pintype "bidirectional"))
    )
    (net (code "79") (name "unconnected-(U1A-PC13-Pad2)") (class "Default")
      (node (ref "U1") (pin "2") (pinfunction "PC13_2") (pintype "bidirectional"))
    )
    (net (code "80") (name "unconnected-(U1A-PC14{slash}OSC32_IN-Pad3)") (class "Default")
      (node (ref "U1") (pin "3") (pinfunction "PC14/OSC32_IN_3") (pintype "bidirectional"))
    )
    (net (code "81") (name "unconnected-(U1A-PC15-OSC32_OUT-Pad4)") (class "Default")
      (node (ref "U1") (pin "4") (pinfunction "PC15-OSC32_OUT_4") (pintype "bidirectional"))
    )
    (net (code "82") (name "unconnected-(U1A-PD2-Pad54)") (class "Default")
      (node (ref "U1") (pin "54") (pinfunction "PD2_54") (pintype "bidirectional"))
    )
    (net (code "83") (name "unconnected-(U1A-PH0{slash}OSC_IN-Pad5)") (class "Default")
      (node (ref "U1") (pin "5") (pinfunction "PH0/OSC_IN_5") (pintype "bidirectional"))
    )
    (net (code "84") (name "unconnected-(U1A-PH1{slash}OSC_OUT-Pad6)") (class "Default")
      (node (ref "U1") (pin "6") (pinfunction "PH1/OSC_OUT_6") (pintype "bidirectional"))
    )
  )
)
